# IO_Combo_USB_Serial.net
KiCad netlist of a schematic drawn in Altium Designer
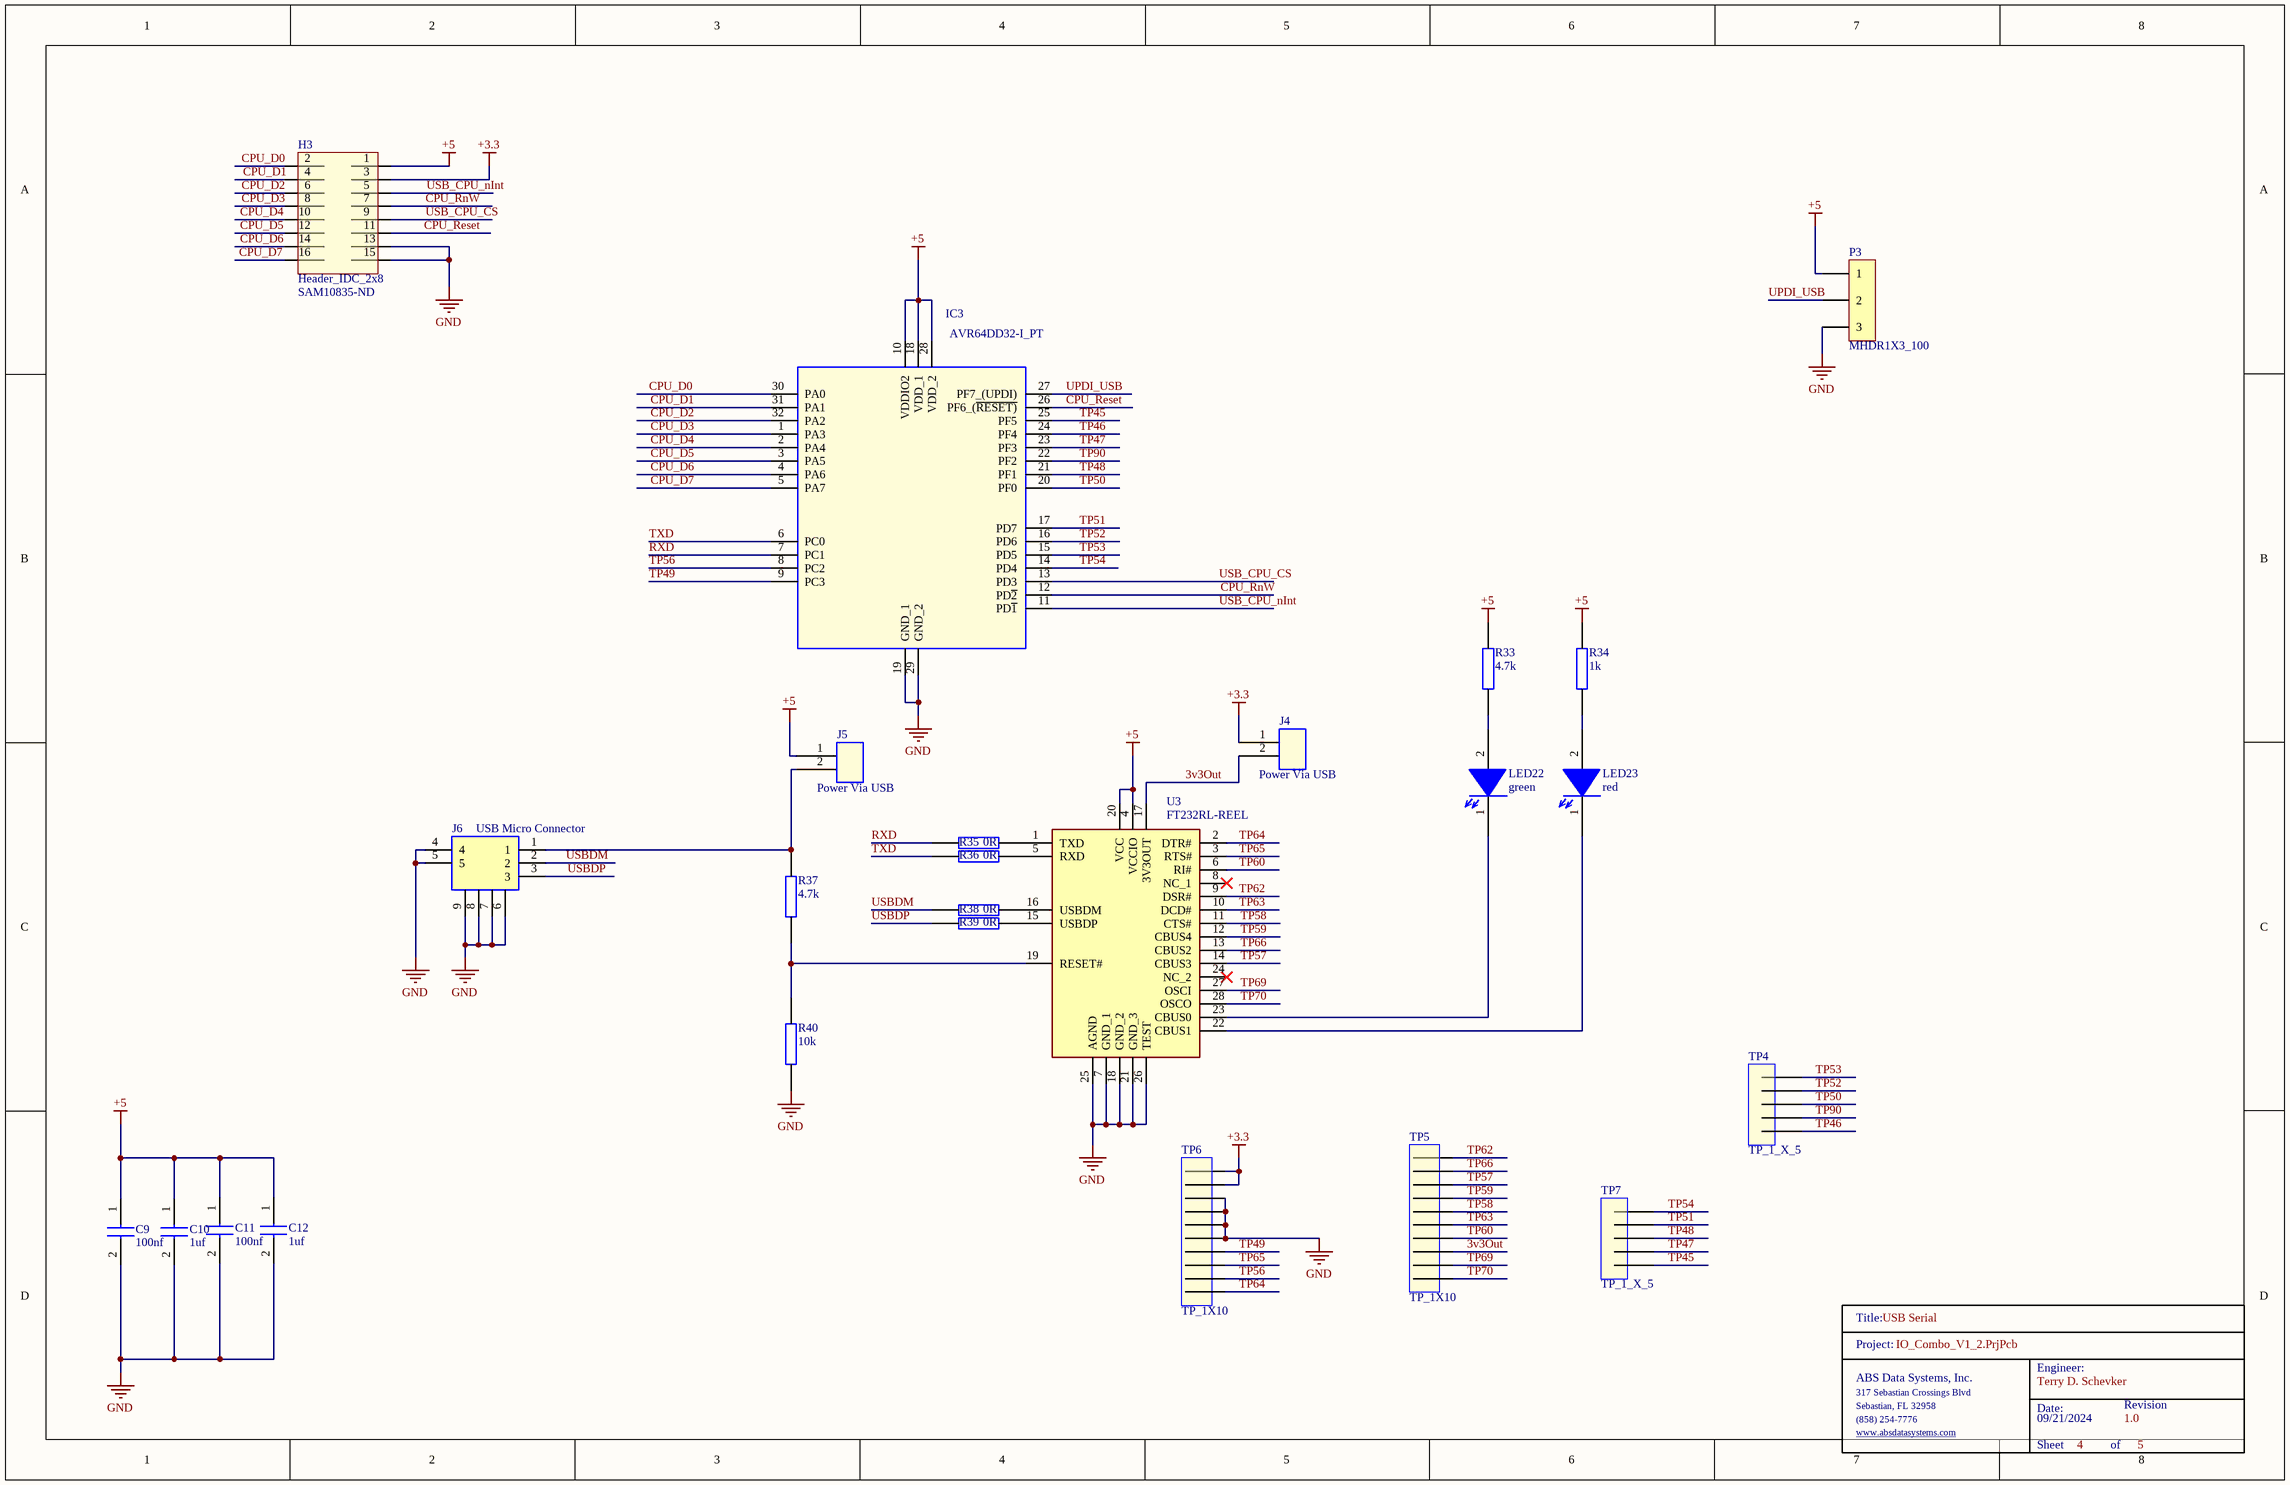
[diagram p0: IO_Combo_USB_Serial.SchDoc]

(export (version "E")
  (design (tool "Eeschema 10.0.6"))
  (components
    (comp (ref "C9")
      (value "100nf")
      (footprint "0603")
      (description "Samsung Electro-Mechanics 0603 100nf")
      (libsource (lib "Capacitors") (part "CL10B104JB8NNNC"))
    )
    (comp (ref "C10")
      (value "1uf")
      (footprint "0603")
      (description "Samsung Electro-Mechanics 0603 1uf")
      (libsource (lib "Capacitors") (part "CL10B105KA8NNNL"))
    )
    (comp (ref "C11")
      (value "100nf")
      (footprint "0603")
      (description "Samsung Electro-Mechanics 0603 100nf")
      (libsource (lib "Capacitors") (part "CL10B104JB8NNNC"))
    )
    (comp (ref "C12")
      (value "1uf")
      (footprint "0603")
      (description "Samsung Electro-Mechanics 0603 1uf")
      (libsource (lib "Capacitors") (part "CL10B105KA8NNNL"))
    )
    (comp (ref "H3")
      (value "Header_IDC_2x8")
      (footprint "HEADER16")
      (description "16 Pin 2x8 Through Hold IDC Connector")
      (fields
        (field (name "MANUFACTURER") "Samtec")
        (field (name "MANUFACTURER PART NUMBER") "TST-108-01-G-D")
        (field (name "SUPPLIER PART NUMBER 1") "SAM10835-ND")
      )
      (libsource (lib "Misc") (part "Header_IDC_2x8"))
    )
    (comp (ref "IC3")
      (value "AVR64DD32-I_PT")
      (footprint "CPU_Memory:QFP80P900X900X120-32N")
      (description "Integrated Circuit")
      (fields (field (name "MANUFACTURER_PART_NUMBER") "AVR64DD32-I/PT ¦ MULTI-VOLTAGE I/O"))
      (libsource (lib "CPU_Memory") (part "AVR64DD32-I_PT"))
    )
    (comp (ref "J4")
      (value "Power Via USB")
      (footprint "Jumper")
      (description "16 Pin 3x8 Through Hold Jumprts")
      (fields
        (field (name "MANUFACTURER") "Samtec")
        (field (name "MANUFACTURER PART NUMBER") "TST-108-01-G-D")
      )
      (libsource (lib "Misc") (part "Jumper"))
    )
    (comp (ref "J5")
      (value "Power Via USB")
      (footprint "Jumper")
      (description "16 Pin 3x8 Through Hold Jumprts")
      (fields
        (field (name "MANUFACTURER") "Samtec")
        (field (name "MANUFACTURER PART NUMBER") "TST-108-01-G-D")
      )
      (libsource (lib "Misc") (part "Jumper"))
    )
    (comp (ref "J6")
      (value "USB Micro Connector")
      (footprint "Connectors:1734035-2USB")
      (description "USB Micro Connector SMD")
      (fields
        (field (name "MOUSER2 PART NUMBER") "571-1734035-4")
        (field (name "MANUFACTURER_PART_NUMBER") "1734035-4")
      )
      (libsource (lib "Connectors") (part "1734035-4"))
    )
    (comp (ref "LED22")
      (value "green")
      (footprint "0603_Diode")
      (description "Wurth Elektronik 0603 green")
      (fields
        (field (name "MANUFACTURER") "Wurth Electronics")
        (field (name "MANUFACTURER PART NUMBER") "150060GS75000")
      )
      (libsource (lib "Misc") (part "150060GS75000"))
    )
    (comp (ref "LED23")
      (value "red")
      (footprint "0603_Diode")
      (description "Wurth Elektronik 0603 red")
      (fields
        (field (name "MANUFACTURER") "Wurth Electronics")
        (field (name "MANUFACTURER PART NUMBER") "150060GS75000")
      )
      (libsource (lib "Misc") (part "150060RS75000"))
    )
    (comp (ref "P3")
      (value "MHDR1X3_100")
      (footprint "MHDR1X3_100")
      (description "Header, 3-Pin")
      (fields (field (name "PUBLISHER") "Altium Limited"))
      (libsource (lib "Connectors") (part "MHDR1X3_100"))
    )
    (comp (ref "R33")
      (value "4.7k")
      (footprint "0603")
      (description "YAGEO 0603 4.7k")
      (fields
        (field (name "MOUSER PART NUMBER") "603-RC0603JR-070RL")
        (field (name "MANUFACTURER_PART_NUMBER") "RC0603JR-070RL")
      )
      (libsource (lib "Resistors") (part "RC0603FR-104K7L"))
    )
    (comp (ref "R34")
      (value "1k")
      (footprint "0603")
      (description "YAGEO 0603 1k ohm")
      (fields
        (field (name "MOUSER PART NUMBER") "603-RC0603JR-070RL")
        (field (name "MANUFACTURER_PART_NUMBER") "RC0603JR-070RL")
      )
      (libsource (lib "Resistors") (part "AC0603FR-7W1KL_1"))
    )
    (comp (ref "R35")
      (value "0R")
      (footprint "0603")
      (description "YAGEO 0603 0 ohm")
      (fields
        (field (name "MOUSER PART NUMBER") "603-RC0603JR-070RL")
        (field (name "MANUFACTURER_PART_NUMBER") "RC0603JR-070RL")
      )
      (libsource (lib "Resistors") (part "RC0603JR-070RL"))
    )
    (comp (ref "R36")
      (value "0R")
      (footprint "0603")
      (description "YAGEO 0603 0 ohm")
      (fields
        (field (name "MOUSER PART NUMBER") "603-RC0603JR-070RL")
        (field (name "MANUFACTURER_PART_NUMBER") "RC0603JR-070RL")
      )
      (libsource (lib "Resistors") (part "RC0603JR-070RL"))
    )
    (comp (ref "R37")
      (value "4.7k")
      (footprint "0603")
      (description "YAGEO 0603 4.7k")
      (fields
        (field (name "MOUSER PART NUMBER") "603-RC0603JR-070RL")
        (field (name "MANUFACTURER_PART_NUMBER") "RC0603JR-070RL")
      )
      (libsource (lib "Resistors") (part "RC0603FR-104K7L"))
    )
    (comp (ref "R38")
      (value "0R")
      (footprint "0603")
      (description "YAGEO 0603 0 ohm")
      (fields
        (field (name "MOUSER PART NUMBER") "603-RC0603JR-070RL")
        (field (name "MANUFACTURER_PART_NUMBER") "RC0603JR-070RL")
      )
      (libsource (lib "Resistors") (part "RC0603JR-070RL"))
    )
    (comp (ref "R39")
      (value "0R")
      (footprint "0603")
      (description "YAGEO 0603 0 ohm")
      (fields
        (field (name "MOUSER PART NUMBER") "603-RC0603JR-070RL")
        (field (name "MANUFACTURER_PART_NUMBER") "RC0603JR-070RL")
      )
      (libsource (lib "Resistors") (part "RC0603JR-070RL"))
    )
    (comp (ref "R40")
      (value "10k")
      (footprint "0603")
      (description "YAGEO 0603 10k ohm")
      (fields
        (field (name "MOUSER PART NUMBER") "603-RC0603JR-070RL")
        (field (name "MANUFACTURER_PART_NUMBER") "RC0603JR-070RL")
      )
      (libsource (lib "Resistors") (part "RC0603JR-0710KL"))
    )
    (comp (ref "TP4")
      (value "TP_1_X_5")
      (footprint "TP_1X5")
      (fields
        (field (name "MANUFACTURER") "Samtec")
        (field (name "MANUFACTURER PART NUMBER") "TST-105-01-G-D")
      )
      (libsource (lib "Misc") (part "TP_1_X_5"))
    )
    (comp (ref "TP5")
      (value "TP_1X10")
      (footprint "TP_1X10")
      (fields
        (field (name "MANUFACTURER") "Samtec")
        (field (name "MANUFACTURER PART NUMBER") "TST-105-01-G-D")
      )
      (libsource (lib "Misc") (part "TP_1X10"))
    )
    (comp (ref "TP6")
      (value "TP_1X10")
      (footprint "TP_1X10")
      (fields
        (field (name "MANUFACTURER") "Samtec")
        (field (name "MANUFACTURER PART NUMBER") "TST-105-01-G-D")
      )
      (libsource (lib "Misc") (part "TP_1X10"))
    )
    (comp (ref "TP7")
      (value "TP_1_X_5")
      (footprint "TP_1X5")
      (fields
        (field (name "MANUFACTURER") "Samtec")
        (field (name "MANUFACTURER PART NUMBER") "TST-105-01-G-D")
      )
      (libsource (lib "Misc") (part "TP_1_X_5"))
    )
    (comp (ref "U3")
      (value "FT232RL-REEL")
      (footprint "Misc:SOIC-28_Narrow")
      (description "USB-Serial SMD")
      (libsource (lib "Misc") (part "FT232RL-REEL"))
    )
  )
  (nets
    (net (code "1") (name "+3.3") (class "Default")
      (node (ref "H3") (pin "3") (pinfunction "3_3") (pintype "passive"))
      (node (ref "J4") (pin "1") (pinfunction "1_1") (pintype "passive"))
      (node (ref "TP6") (pin "1") (pinfunction "1_1") (pintype "passive"))
      (node (ref "TP6") (pin "2") (pinfunction "2_2") (pintype "passive"))
    )
    (net (code "2") (name "+5") (class "Default")
      (node (ref "C10") (pin "1") (pinfunction "1_1") (pintype "passive"))
      (node (ref "C11") (pin "1") (pinfunction "1_1") (pintype "passive"))
      (node (ref "C12") (pin "1") (pinfunction "1_1") (pintype "passive"))
      (node (ref "C9") (pin "1") (pinfunction "1_1") (pintype "passive"))
      (node (ref "H3") (pin "1") (pinfunction "1_1") (pintype "passive"))
      (node (ref "IC3") (pin "10") (pinfunction "VDDIO2_10") (pintype "passive"))
      (node (ref "IC3") (pin "18") (pinfunction "VDD_1_18") (pintype "passive"))
      (node (ref "IC3") (pin "28") (pinfunction "VDD_2_28") (pintype "passive"))
      (node (ref "J5") (pin "1") (pinfunction "1_1") (pintype "passive"))
      (node (ref "P3") (pin "1") (pinfunction "1_1") (pintype "passive"))
      (node (ref "R33") (pin "2") (pinfunction "2_2") (pintype "passive"))
      (node (ref "R34") (pin "2") (pinfunction "2_2") (pintype "passive"))
      (node (ref "U3") (pin "20") (pinfunction "VCC_20") (pintype "passive"))
      (node (ref "U3") (pin "4") (pinfunction "VCCIO_4") (pintype "passive"))
    )
    (net (code "3") (name "/3v3Out") (class "Default")
      (node (ref "J4") (pin "2") (pinfunction "2_2") (pintype "passive"))
      (node (ref "TP5") (pin "8") (pinfunction "8_8") (pintype "passive"))
      (node (ref "U3") (pin "17") (pinfunction "3V3OUT_17") (pintype "passive"))
    )
    (net (code "4") (name "/CPU_D0") (class "Default")
      (node (ref "H3") (pin "2") (pinfunction "2_2") (pintype "passive"))
      (node (ref "IC3") (pin "30") (pinfunction "PA0_30") (pintype "passive"))
    )
    (net (code "5") (name "/CPU_D1") (class "Default")
      (node (ref "H3") (pin "4") (pinfunction "4_4") (pintype "passive"))
      (node (ref "IC3") (pin "31") (pinfunction "PA1_31") (pintype "passive"))
    )
    (net (code "6") (name "/CPU_D2") (class "Default")
      (node (ref "H3") (pin "6") (pinfunction "6_6") (pintype "passive"))
      (node (ref "IC3") (pin "32") (pinfunction "PA2_32") (pintype "passive"))
    )
    (net (code "7") (name "/CPU_D3") (class "Default")
      (node (ref "H3") (pin "8") (pinfunction "8_8") (pintype "passive"))
      (node (ref "IC3") (pin "1") (pinfunction "PA3_1") (pintype "passive"))
    )
    (net (code "8") (name "/CPU_D4") (class "Default")
      (node (ref "H3") (pin "10") (pinfunction "10_10") (pintype "passive"))
      (node (ref "IC3") (pin "2") (pinfunction "PA4_2") (pintype "passive"))
    )
    (net (code "9") (name "/CPU_D5") (class "Default")
      (node (ref "H3") (pin "12") (pinfunction "12_12") (pintype "passive"))
      (node (ref "IC3") (pin "3") (pinfunction "PA5_3") (pintype "passive"))
    )
    (net (code "10") (name "/CPU_D6") (class "Default")
      (node (ref "H3") (pin "14") (pinfunction "14_14") (pintype "passive"))
      (node (ref "IC3") (pin "4") (pinfunction "PA6_4") (pintype "passive"))
    )
    (net (code "11") (name "/CPU_D7") (class "Default")
      (node (ref "H3") (pin "16") (pinfunction "16_16") (pintype "passive"))
      (node (ref "IC3") (pin "5") (pinfunction "PA7_5") (pintype "passive"))
    )
    (net (code "12") (name "/CPU_Reset") (class "Default")
      (node (ref "H3") (pin "11") (pinfunction "11_11") (pintype "passive"))
      (node (ref "IC3") (pin "26") (pinfunction "PF6_(~{RESET)}_26") (pintype "passive"))
    )
    (net (code "13") (name "/CPU_RnW") (class "Default")
      (node (ref "H3") (pin "7") (pinfunction "7_7") (pintype "passive"))
      (node (ref "IC3") (pin "12") (pinfunction "PD~{2}_12") (pintype "passive"))
    )
    (net (code "14") (name "/RXD") (class "Default")
      (node (ref "IC3") (pin "7") (pinfunction "PC1_7") (pintype "passive"))
      (node (ref "R35") (pin "1") (pinfunction "1_1") (pintype "passive"))
    )
    (net (code "15") (name "/TP45") (class "Default")
      (node (ref "IC3") (pin "25") (pinfunction "PF5_25") (pintype "passive"))
      (node (ref "TP7") (pin "5") (pinfunction "5_5") (pintype "passive"))
    )
    (net (code "16") (name "/TP46") (class "Default")
      (node (ref "IC3") (pin "24") (pinfunction "PF4_24") (pintype "passive"))
      (node (ref "TP4") (pin "5") (pinfunction "5_5") (pintype "passive"))
    )
    (net (code "17") (name "/TP47") (class "Default")
      (node (ref "IC3") (pin "23") (pinfunction "PF3_23") (pintype "passive"))
      (node (ref "TP7") (pin "4") (pinfunction "4_4") (pintype "passive"))
    )
    (net (code "18") (name "/TP48") (class "Default")
      (node (ref "IC3") (pin "21") (pinfunction "PF1_21") (pintype "passive"))
      (node (ref "TP7") (pin "3") (pinfunction "3_3") (pintype "passive"))
    )
    (net (code "19") (name "/TP49") (class "Default")
      (node (ref "IC3") (pin "9") (pinfunction "PC3_9") (pintype "passive"))
      (node (ref "TP6") (pin "7") (pinfunction "7_7") (pintype "passive"))
    )
    (net (code "20") (name "/TP50") (class "Default")
      (node (ref "IC3") (pin "20") (pinfunction "PF0_20") (pintype "passive"))
      (node (ref "TP4") (pin "3") (pinfunction "3_3") (pintype "passive"))
    )
    (net (code "21") (name "/TP51") (class "Default")
      (node (ref "IC3") (pin "17") (pinfunction "PD7_17") (pintype "passive"))
      (node (ref "TP7") (pin "2") (pinfunction "2_2") (pintype "passive"))
    )
    (net (code "22") (name "/TP52") (class "Default")
      (node (ref "IC3") (pin "16") (pinfunction "PD6_16") (pintype "passive"))
      (node (ref "TP4") (pin "2") (pinfunction "2_2") (pintype "passive"))
    )
    (net (code "23") (name "/TP53") (class "Default")
      (node (ref "IC3") (pin "15") (pinfunction "PD5_15") (pintype "passive"))
      (node (ref "TP4") (pin "1") (pinfunction "1_1") (pintype "passive"))
    )
    (net (code "24") (name "/TP54") (class "Default")
      (node (ref "IC3") (pin "14") (pinfunction "PD4_14") (pintype "passive"))
      (node (ref "TP7") (pin "1") (pinfunction "1_1") (pintype "passive"))
    )
    (net (code "25") (name "/TP56") (class "Default")
      (node (ref "IC3") (pin "8") (pinfunction "PC2_8") (pintype "passive"))
      (node (ref "TP6") (pin "9") (pinfunction "9_9") (pintype "passive"))
    )
    (net (code "26") (name "/TP57") (class "Default")
      (node (ref "TP5") (pin "3") (pinfunction "3_3") (pintype "passive"))
      (node (ref "U3") (pin "14") (pinfunction "CBUS3_14") (pintype "passive"))
    )
    (net (code "27") (name "/TP58") (class "Default")
      (node (ref "TP5") (pin "5") (pinfunction "5_5") (pintype "passive"))
      (node (ref "U3") (pin "11") (pinfunction "CTS#_11") (pintype "passive"))
    )
    (net (code "28") (name "/TP59") (class "Default")
      (node (ref "TP5") (pin "4") (pinfunction "4_4") (pintype "passive"))
      (node (ref "U3") (pin "12") (pinfunction "CBUS4_12") (pintype "passive"))
    )
    (net (code "29") (name "/TP60") (class "Default")
      (node (ref "TP5") (pin "7") (pinfunction "7_7") (pintype "passive"))
      (node (ref "U3") (pin "6") (pinfunction "RI#_6") (pintype "passive"))
    )
    (net (code "30") (name "/TP62") (class "Default")
      (node (ref "TP5") (pin "1") (pinfunction "1_1") (pintype "passive"))
      (node (ref "U3") (pin "9") (pinfunction "DSR#_9") (pintype "passive"))
    )
    (net (code "31") (name "/TP63") (class "Default")
      (node (ref "TP5") (pin "6") (pinfunction "6_6") (pintype "passive"))
      (node (ref "U3") (pin "10") (pinfunction "DCD#_10") (pintype "passive"))
    )
    (net (code "32") (name "/TP64") (class "Default")
      (node (ref "TP6") (pin "10") (pinfunction "10_10") (pintype "passive"))
      (node (ref "U3") (pin "2") (pinfunction "DTR#_2") (pintype "passive"))
    )
    (net (code "33") (name "/TP65") (class "Default")
      (node (ref "TP6") (pin "8") (pinfunction "8_8") (pintype "passive"))
      (node (ref "U3") (pin "3") (pinfunction "RTS#_3") (pintype "passive"))
    )
    (net (code "34") (name "/TP66") (class "Default")
      (node (ref "TP5") (pin "2") (pinfunction "2_2") (pintype "passive"))
      (node (ref "U3") (pin "13") (pinfunction "CBUS2_13") (pintype "passive"))
    )
    (net (code "35") (name "/TP69") (class "Default")
      (node (ref "TP5") (pin "9") (pinfunction "9_9") (pintype "passive"))
      (node (ref "U3") (pin "27") (pinfunction "OSCI_27") (pintype "passive"))
    )
    (net (code "36") (name "/TP70") (class "Default")
      (node (ref "TP5") (pin "10") (pinfunction "10_10") (pintype "passive"))
      (node (ref "U3") (pin "28") (pinfunction "OSCO_28") (pintype "passive"))
    )
    (net (code "37") (name "/TP90") (class "Default")
      (node (ref "IC3") (pin "22") (pinfunction "PF2_22") (pintype "passive"))
      (node (ref "TP4") (pin "4") (pinfunction "4_4") (pintype "passive"))
    )
    (net (code "38") (name "/TXD") (class "Default")
      (node (ref "IC3") (pin "6") (pinfunction "PC0_6") (pintype "passive"))
      (node (ref "R36") (pin "1") (pinfunction "1_1") (pintype "passive"))
    )
    (net (code "39") (name "/UPDI_USB") (class "Default")
      (node (ref "IC3") (pin "27") (pinfunction "PF7_(UPDI)_27") (pintype "passive"))
      (node (ref "P3") (pin "2") (pinfunction "2_2") (pintype "passive"))
    )
    (net (code "40") (name "/USBDM") (class "Default")
      (node (ref "J6") (pin "2") (pinfunction "2_2") (pintype "passive"))
      (node (ref "R38") (pin "1") (pinfunction "1_1") (pintype "passive"))
    )
    (net (code "41") (name "/USBDP") (class "Default")
      (node (ref "J6") (pin "3") (pinfunction "3_3") (pintype "passive"))
      (node (ref "R39") (pin "1") (pinfunction "1_1") (pintype "passive"))
    )
    (net (code "42") (name "/USB_CPU_CS") (class "Default")
      (node (ref "H3") (pin "9") (pinfunction "9_9") (pintype "passive"))
      (node (ref "IC3") (pin "13") (pinfunction "PD3_13") (pintype "passive"))
    )
    (net (code "43") (name "/USB_CPU_nInt") (class "Default")
      (node (ref "H3") (pin "5") (pinfunction "5_5") (pintype "passive"))
      (node (ref "IC3") (pin "11") (pinfunction "PD~{1}_11") (pintype "passive"))
    )
    (net (code "44") (name "GND") (class "Default")
      (node (ref "C10") (pin "2") (pinfunction "2_2") (pintype "passive"))
      (node (ref "C11") (pin "2") (pinfunction "2_2") (pintype "passive"))
      (node (ref "C12") (pin "2") (pinfunction "2_2") (pintype "passive"))
      (node (ref "C9") (pin "2") (pinfunction "2_2") (pintype "passive"))
      (node (ref "H3") (pin "13") (pinfunction "13_13") (pintype "passive"))
      (node (ref "H3") (pin "15") (pinfunction "15_15") (pintype "passive"))
      (node (ref "IC3") (pin "19") (pinfunction "GND_1_19") (pintype "passive"))
      (node (ref "IC3") (pin "29") (pinfunction "GND_2_29") (pintype "passive"))
      (node (ref "J6") (pin "4") (pinfunction "4_4") (pintype "passive"))
      (node (ref "J6") (pin "5") (pinfunction "5_5") (pintype "passive"))
      (node (ref "J6") (pin "6") (pinfunction "Shield_6") (pintype "passive"))
      (node (ref "J6") (pin "7") (pinfunction "Shield_7") (pintype "passive"))
      (node (ref "J6") (pin "8") (pinfunction "Shield_8") (pintype "passive"))
      (node (ref "J6") (pin "9") (pinfunction "Shield5_9") (pintype "passive"))
      (node (ref "P3") (pin "3") (pinfunction "3_3") (pintype "passive"))
      (node (ref "R40") (pin "1") (pinfunction "1_1") (pintype "passive"))
      (node (ref "TP6") (pin "3") (pinfunction "3_3") (pintype "passive"))
      (node (ref "TP6") (pin "4") (pinfunction "4_4") (pintype "passive"))
      (node (ref "TP6") (pin "5") (pinfunction "5_5") (pintype "passive"))
      (node (ref "TP6") (pin "6") (pinfunction "6_6") (pintype "passive"))
      (node (ref "U3") (pin "18") (pinfunction "GND_2_18") (pintype "passive"))
      (node (ref "U3") (pin "21") (pinfunction "GND_3_21") (pintype "passive"))
      (node (ref "U3") (pin "25") (pinfunction "AGND_25") (pintype "passive"))
      (node (ref "U3") (pin "26") (pinfunction "TEST_26") (pintype "passive"))
      (node (ref "U3") (pin "7") (pinfunction "GND_1_7") (pintype "passive"))
    )
    (net (code "45") (name "Net-(J5-Pad2)") (class "Default")
      (node (ref "J5") (pin "2") (pinfunction "2_2") (pintype "passive"))
      (node (ref "J6") (pin "1") (pinfunction "1_1") (pintype "passive"))
      (node (ref "R37") (pin "2") (pinfunction "2_2") (pintype "passive"))
    )
    (net (code "46") (name "Net-(LED22-A)") (class "Default")
      (node (ref "LED22") (pin "2") (pinfunction "A_2") (pintype "passive"))
      (node (ref "R33") (pin "1") (pinfunction "1_1") (pintype "passive"))
    )
    (net (code "47") (name "Net-(LED22-K)") (class "Default")
      (node (ref "LED22") (pin "1") (pinfunction "K_1") (pintype "passive"))
      (node (ref "U3") (pin "23") (pinfunction "CBUS0_23") (pintype "passive"))
    )
    (net (code "48") (name "Net-(LED23-A)") (class "Default")
      (node (ref "LED23") (pin "2") (pinfunction "A_2") (pintype "passive"))
      (node (ref "R34") (pin "1") (pinfunction "1_1") (pintype "passive"))
    )
    (net (code "49") (name "Net-(LED23-K)") (class "Default")
      (node (ref "LED23") (pin "1") (pinfunction "K_1") (pintype "passive"))
      (node (ref "U3") (pin "22") (pinfunction "CBUS1_22") (pintype "passive"))
    )
    (net (code "50") (name "Net-(U3-RESET#)") (class "Default")
      (node (ref "R37") (pin "1") (pinfunction "1_1") (pintype "passive"))
      (node (ref "R40") (pin "2") (pinfunction "2_2") (pintype "passive"))
      (node (ref "U3") (pin "19") (pinfunction "RESET#_19") (pintype "passive"))
    )
    (net (code "51") (name "Net-(U3-RXD)") (class "Default")
      (node (ref "R36") (pin "2") (pinfunction "2_2") (pintype "passive"))
      (node (ref "U3") (pin "5") (pinfunction "RXD_5") (pintype "passive"))
    )
    (net (code "52") (name "Net-(U3-TXD)") (class "Default")
      (node (ref "R35") (pin "2") (pinfunction "2_2") (pintype "passive"))
      (node (ref "U3") (pin "1") (pinfunction "TXD_1") (pintype "passive"))
    )
    (net (code "53") (name "Net-(U3-USBDM)") (class "Default")
      (node (ref "R38") (pin "2") (pinfunction "2_2") (pintype "passive"))
      (node (ref "U3") (pin "16") (pinfunction "USBDM_16") (pintype "passive"))
    )
    (net (code "54") (name "Net-(U3-USBDP)") (class "Default")
      (node (ref "R39") (pin "2") (pinfunction "2_2") (pintype "passive"))
      (node (ref "U3") (pin "15") (pinfunction "USBDP_15") (pintype "passive"))
    )
    (net (code "55") (name "unconnected-(U3-NC_1-Pad8)") (class "Default")
      (node (ref "U3") (pin "8") (pinfunction "NC_1_8") (pintype "passive+no_connect"))
    )
    (net (code "56") (name "unconnected-(U3-NC_2-Pad24)") (class "Default")
      (node (ref "U3") (pin "24") (pinfunction "NC_2_24") (pintype "passive+no_connect"))
    )
  )
)
